# quantum_PSU_V2_3.net
KiCad netlist of a schematic drawn in EAGLE
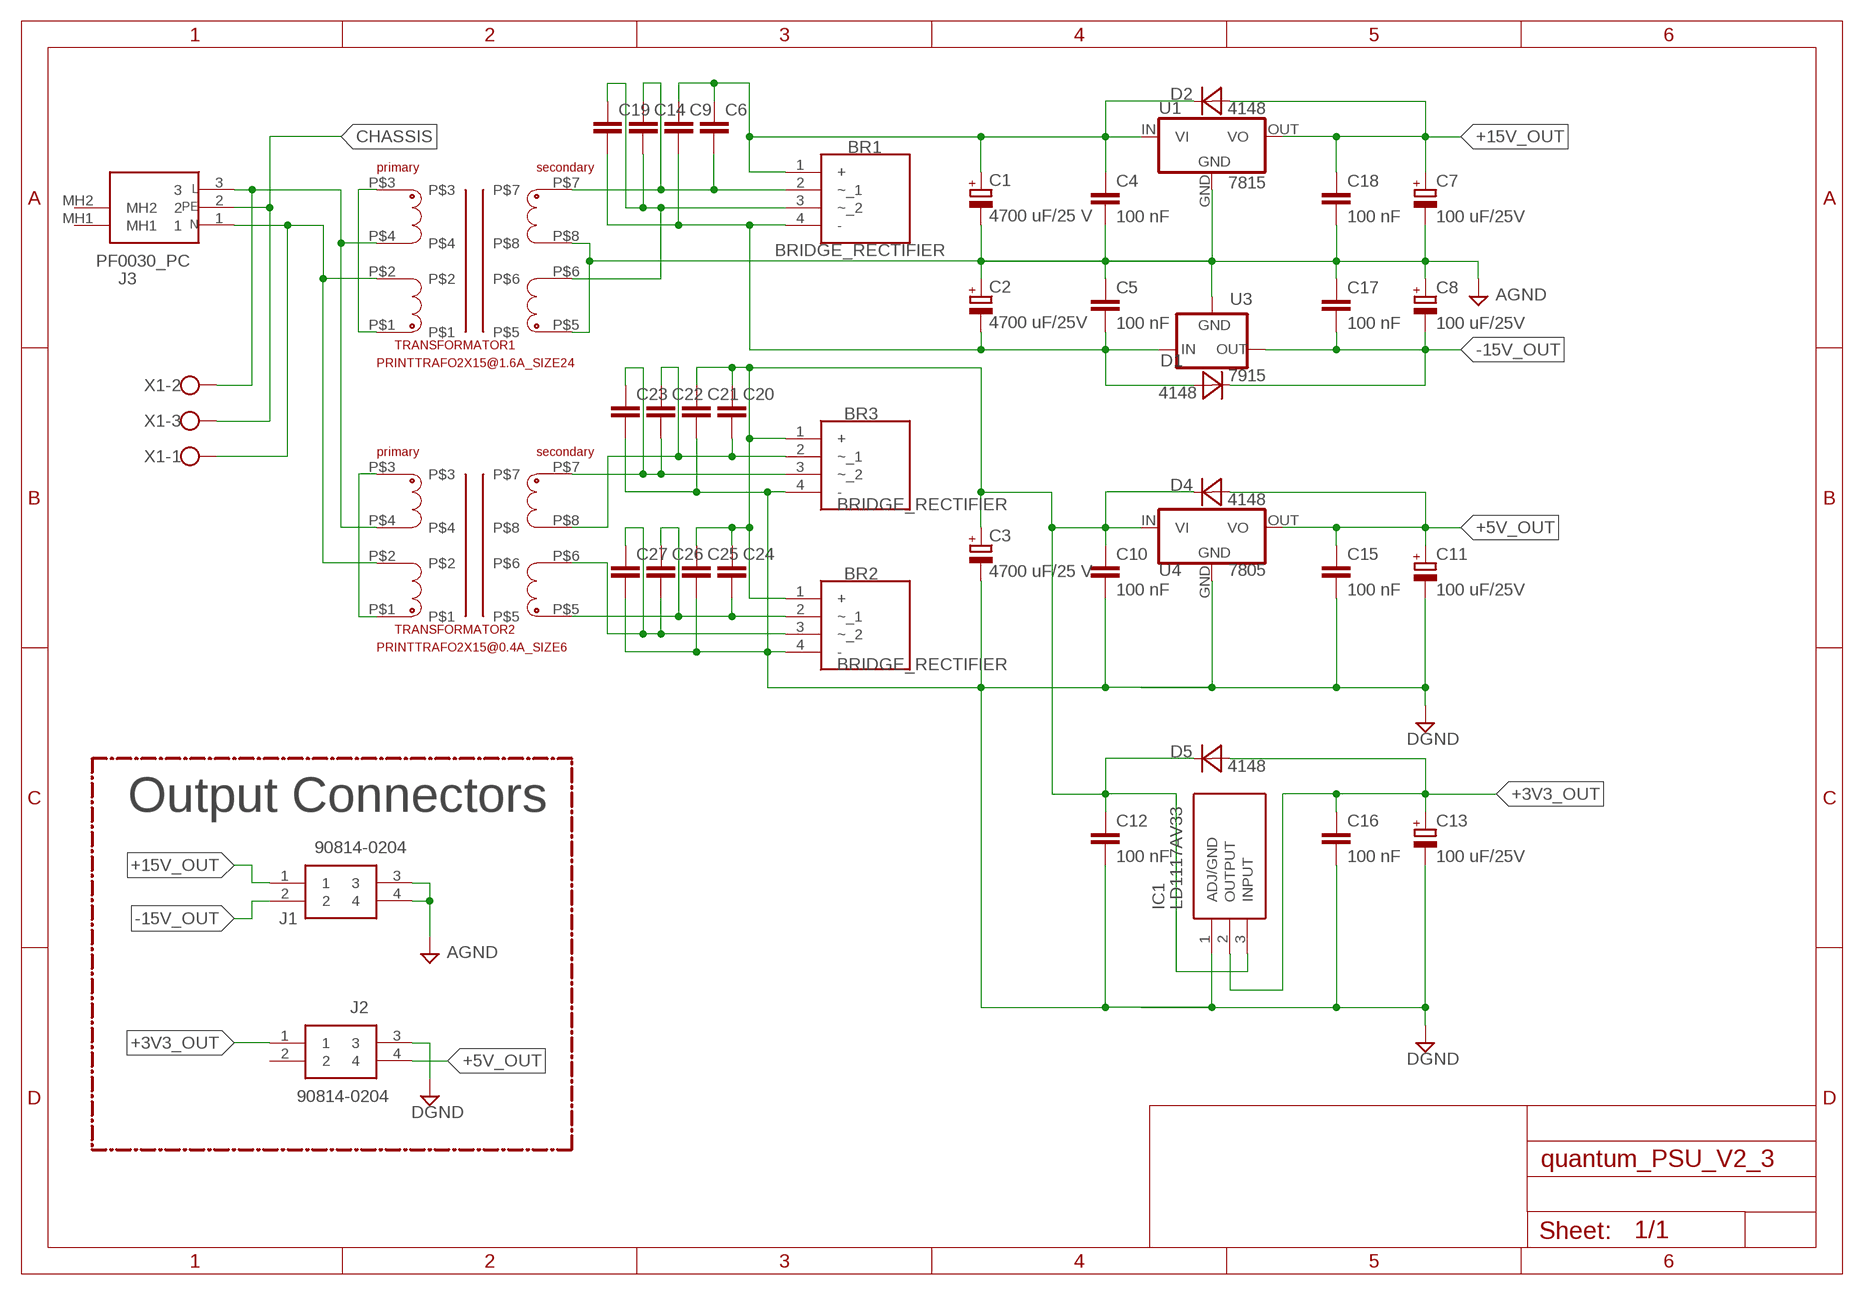
[diagram p0: schematic, sheet 1]

(export (version "E")
  (design (tool "Eeschema 10.0.6"))
  (components
    (comp (ref "BR1")
      (value "BRIDGE_RECTIFIER")
      (footprint "eagle-import:KBP308G")
      (fields
        (field (name "MANUFACTURER_PART_NUMBER") "KBP308G")
        (field (name "MOUSER_PART_NUMBER") "621-KBP308G")
      )
      (libsource (lib "eagle-import") (part "BRIDGE_RECTIFIER"))
    )
    (comp (ref "BR2")
      (value "BRIDGE_RECTIFIER")
      (footprint "eagle-import:KBP308G")
      (fields
        (field (name "MANUFACTURER_PART_NUMBER") "KBP308G")
        (field (name "MOUSER_PART_NUMBER") "621-KBP308G")
      )
      (libsource (lib "eagle-import") (part "BRIDGE_RECTIFIER"))
    )
    (comp (ref "BR3")
      (value "BRIDGE_RECTIFIER")
      (footprint "eagle-import:KBP308G")
      (fields
        (field (name "MANUFACTURER_PART_NUMBER") "KBP308G")
        (field (name "MOUSER_PART_NUMBER") "621-KBP308G")
      )
      (libsource (lib "eagle-import") (part "BRIDGE_RECTIFIER"))
    )
    (comp (ref "C1")
      (value "4700 uF/25 V")
      (footprint "eagle-import:ELECTROLYTIC_16MM")
      (libsource (lib "eagle-import") (part "CAPACITOR_ELECTROLYTIC_16MM-THT"))
    )
    (comp (ref "C2")
      (value "4700 uF/25V")
      (footprint "eagle-import:ELECTROLYTIC_16MM")
      (libsource (lib "eagle-import") (part "CAPACITOR_ELECTROLYTIC_16MM-THT"))
    )
    (comp (ref "C3")
      (value "4700 uF/25 V")
      (footprint "eagle-import:ELECTROLYTIC_16MM")
      (libsource (lib "eagle-import") (part "CAPACITOR_ELECTROLYTIC_16MM-THT"))
    )
    (comp (ref "C4")
      (value "100 nF")
      (footprint "eagle-import:C5MM")
      (libsource (lib "eagle-import") (part "CAPACITOR_5MM"))
    )
    (comp (ref "C5")
      (value "100 nF")
      (footprint "eagle-import:C5MM")
      (libsource (lib "eagle-import") (part "CAPACITOR_5MM"))
    )
    (comp (ref "C6")
      (value "CAPACITOR_2.5MM")
      (footprint "eagle-import:C2.5MM")
      (libsource (lib "eagle-import") (part "CAPACITOR_2.5MM"))
    )
    (comp (ref "C7")
      (value "100 uF/25V")
      (footprint "eagle-import:ELECTROLYTIC_8MM")
      (libsource (lib "eagle-import") (part "CAPACITOR_ELECTROLYTIC_8MM-THT"))
    )
    (comp (ref "C8")
      (value "100 uF/25V")
      (footprint "eagle-import:ELECTROLYTIC_8MM")
      (libsource (lib "eagle-import") (part "CAPACITOR_ELECTROLYTIC_8MM-THT"))
    )
    (comp (ref "C9")
      (value "CAPACITOR_2.5MM")
      (footprint "eagle-import:C2.5MM")
      (libsource (lib "eagle-import") (part "CAPACITOR_2.5MM"))
    )
    (comp (ref "C10")
      (value "100 nF")
      (footprint "eagle-import:C5MM")
      (libsource (lib "eagle-import") (part "CAPACITOR_5MM"))
    )
    (comp (ref "C11")
      (value "100 uF/25V")
      (footprint "eagle-import:ELECTROLYTIC_8MM")
      (libsource (lib "eagle-import") (part "CAPACITOR_ELECTROLYTIC_8MM-THT"))
    )
    (comp (ref "C12")
      (value "100 nF")
      (footprint "eagle-import:C5MM")
      (libsource (lib "eagle-import") (part "CAPACITOR_5MM"))
    )
    (comp (ref "C13")
      (value "100 uF/25V")
      (footprint "eagle-import:ELECTROLYTIC_8MM")
      (libsource (lib "eagle-import") (part "CAPACITOR_ELECTROLYTIC_8MM-THT"))
    )
    (comp (ref "C14")
      (value "CAPACITOR_2.5MM")
      (footprint "eagle-import:C2.5MM")
      (libsource (lib "eagle-import") (part "CAPACITOR_2.5MM"))
    )
    (comp (ref "C15")
      (value "100 nF")
      (footprint "eagle-import:C5MM")
      (libsource (lib "eagle-import") (part "CAPACITOR_5MM"))
    )
    (comp (ref "C16")
      (value "100 nF")
      (footprint "eagle-import:C5MM")
      (libsource (lib "eagle-import") (part "CAPACITOR_5MM"))
    )
    (comp (ref "C17")
      (value "100 nF")
      (footprint "eagle-import:C5MM")
      (libsource (lib "eagle-import") (part "CAPACITOR_5MM"))
    )
    (comp (ref "C18")
      (value "100 nF")
      (footprint "eagle-import:C5MM")
      (libsource (lib "eagle-import") (part "CAPACITOR_5MM"))
    )
    (comp (ref "C19")
      (value "CAPACITOR_2.5MM")
      (footprint "eagle-import:C2.5MM")
      (libsource (lib "eagle-import") (part "CAPACITOR_2.5MM"))
    )
    (comp (ref "C20")
      (value "CAPACITOR_2.5MM")
      (footprint "eagle-import:C2.5MM")
      (libsource (lib "eagle-import") (part "CAPACITOR_2.5MM"))
    )
    (comp (ref "C21")
      (value "CAPACITOR_2.5MM")
      (footprint "eagle-import:C2.5MM")
      (libsource (lib "eagle-import") (part "CAPACITOR_2.5MM"))
    )
    (comp (ref "C22")
      (value "CAPACITOR_2.5MM")
      (footprint "eagle-import:C2.5MM")
      (libsource (lib "eagle-import") (part "CAPACITOR_2.5MM"))
    )
    (comp (ref "C23")
      (value "CAPACITOR_2.5MM")
      (footprint "eagle-import:C2.5MM")
      (libsource (lib "eagle-import") (part "CAPACITOR_2.5MM"))
    )
    (comp (ref "C24")
      (value "CAPACITOR_2.5MM")
      (footprint "eagle-import:C2.5MM")
      (libsource (lib "eagle-import") (part "CAPACITOR_2.5MM"))
    )
    (comp (ref "C25")
      (value "CAPACITOR_2.5MM")
      (footprint "eagle-import:C2.5MM")
      (libsource (lib "eagle-import") (part "CAPACITOR_2.5MM"))
    )
    (comp (ref "C26")
      (value "CAPACITOR_2.5MM")
      (footprint "eagle-import:C2.5MM")
      (libsource (lib "eagle-import") (part "CAPACITOR_2.5MM"))
    )
    (comp (ref "C27")
      (value "CAPACITOR_2.5MM")
      (footprint "eagle-import:C2.5MM")
      (libsource (lib "eagle-import") (part "CAPACITOR_2.5MM"))
    )
    (comp (ref "D1")
      (value "4148")
      (footprint "eagle-import:DIODE_THT_STANDING")
      (fields (field (name "MOUSER_PART_NUMBER") "..."))
      (libsource (lib "eagle-import") (part "DIODE_4148_THT"))
    )
    (comp (ref "D2")
      (value "4148")
      (footprint "eagle-import:DIODE_THT_STANDING")
      (fields (field (name "MOUSER_PART_NUMBER") "..."))
      (libsource (lib "eagle-import") (part "DIODE_4148_THT"))
    )
    (comp (ref "D4")
      (value "4148")
      (footprint "eagle-import:DIODE_THT_STANDING")
      (fields (field (name "MOUSER_PART_NUMBER") "..."))
      (libsource (lib "eagle-import") (part "DIODE_4148_THT"))
    )
    (comp (ref "D5")
      (value "4148")
      (footprint "eagle-import:DIODE_THT_STANDING")
      (fields (field (name "MOUSER_PART_NUMBER") "..."))
      (libsource (lib "eagle-import") (part "DIODE_4148_THT"))
    )
    (comp (ref "IC1")
      (value "LD1117AV33")
      (footprint "eagle-import:TO255P460X1020X2008-3P")
      (fields (field (name "MOUSER_PART_NUMBER") "511-LD1117AV33"))
      (libsource (lib "eagle-import") (part "LD1117AV33"))
    )
    (comp (ref "J1")
      (value "90814-0204")
      (footprint "eagle-import:MOLEX_90814-0204")
      (fields (field (name "MOUSER_PART_NUMBER") "538-90814-0204"))
      (libsource (lib "eagle-import") (part "90814-0204"))
    )
    (comp (ref "J2")
      (value "90814-0204")
      (footprint "eagle-import:MOLEX_90814-0204")
      (fields (field (name "MOUSER_PART_NUMBER") "538-90814-0204"))
      (libsource (lib "eagle-import") (part "90814-0204"))
    )
    (comp (ref "J3")
      (value "PF0030_PC")
      (footprint "eagle-import:PF0030PC")
      (fields
        (field (name "MANUFACTURER_PART_NUMBER") "PF0030/PC")
        (field (name "MOUSER_PART_NUMBER") "161-PF0030/PC")
      )
      (libsource (lib "eagle-import") (part "PF0030_PC"))
    )
    (comp (ref "TRANSFORMATOR1")
      (value "PRINTTRAFO2X15@1.6A_SIZE24")
      (footprint "eagle-import:LP_SIZE_24")
      (fields (field (name "MOUSER_PART_NUMBER") "530-LP-30-800"))
      (libsource (lib "eagle-import") (part "PRINTTRAFO_SIZE242X15@1.6A"))
    )
    (comp (ref "TRANSFORMATOR2")
      (value "PRINTTRAFO2X15@0.4A_SIZE6")
      (footprint "eagle-import:LP_SIZE_6")
      (fields (field (name "MOUSER_PART_NUMBER") "530-LP-30-200"))
      (libsource (lib "eagle-import") (part "PRINTTRAFO_SIZE62X15@0.4A"))
    )
    (comp (ref "U1")
      (value "7815")
      (footprint "eagle-import:78XXS_")
      (libsource (lib "eagle-import") (part "78_THT"))
    )
    (comp (ref "U3")
      (value "7915")
      (footprint "eagle-import:79XXS")
      (libsource (lib "eagle-import") (part "79_THT"))
    )
    (comp (ref "U4")
      (value "7805")
      (footprint "eagle-import:78XXS_")
      (libsource (lib "eagle-import") (part "78_THT"))
    )
    (comp (ref "X1")
      (value "CONNECTOR_3POL")
      (footprint "eagle-import:W237-103")
      (libsource (lib "eagle-import") (part "CONNECTOR_3POL"))
    )
  )
  (nets
    (net (code "1") (name "+3V3_OUT") (class "Default")
      (node (ref "C13") (pin "+") (pinfunction "+_+") (pintype "passive"))
      (node (ref "C16") (pin "1") (pinfunction "1_1") (pintype "passive"))
      (node (ref "D5") (pin "A") (pinfunction "A_A") (pintype "passive"))
      (node (ref "IC1") (pin "2") (pinfunction "OUTPUT_2") (pintype "bidirectional"))
      (node (ref "J2") (pin "1") (pinfunction "1_1") (pintype "bidirectional"))
    )
    (net (code "2") (name "+5V_OUT") (class "Default")
      (node (ref "C11") (pin "+") (pinfunction "+_+") (pintype "passive"))
      (node (ref "C15") (pin "1") (pinfunction "1_1") (pintype "passive"))
      (node (ref "D4") (pin "A") (pinfunction "A_A") (pintype "passive"))
      (node (ref "J2") (pin "4") (pinfunction "4_4") (pintype "bidirectional"))
      (node (ref "U4") (pin "OUT") (pinfunction "VO_OUT") (pintype "passive"))
    )
    (net (code "3") (name "+15V_OUT") (class "Default")
      (node (ref "C18") (pin "1") (pinfunction "1_1") (pintype "passive"))
      (node (ref "C7") (pin "+") (pinfunction "+_+") (pintype "passive"))
      (node (ref "D2") (pin "A") (pinfunction "A_A") (pintype "passive"))
      (node (ref "J1") (pin "1") (pinfunction "1_1") (pintype "bidirectional"))
      (node (ref "U1") (pin "OUT") (pinfunction "VO_OUT") (pintype "passive"))
    )
    (net (code "4") (name "-15V_OUT") (class "Default")
      (node (ref "C17") (pin "2") (pinfunction "2_2") (pintype "passive"))
      (node (ref "C8") (pin "-") (pinfunction "-_-") (pintype "passive"))
      (node (ref "D1") (pin "C") (pinfunction "C_C") (pintype "passive"))
      (node (ref "J1") (pin "2") (pinfunction "2_2") (pintype "bidirectional"))
      (node (ref "U3") (pin "OUT") (pinfunction "OUT_OUT") (pintype "passive"))
    )
    (net (code "5") (name "AGND") (class "Default")
      (node (ref "C1") (pin "-") (pinfunction "-_-") (pintype "passive"))
      (node (ref "C17") (pin "1") (pinfunction "1_1") (pintype "passive"))
      (node (ref "C18") (pin "2") (pinfunction "2_2") (pintype "passive"))
      (node (ref "C2") (pin "+") (pinfunction "+_+") (pintype "passive"))
      (node (ref "C4") (pin "2") (pinfunction "2_2") (pintype "passive"))
      (node (ref "C5") (pin "1") (pinfunction "1_1") (pintype "passive"))
      (node (ref "C7") (pin "-") (pinfunction "-_-") (pintype "passive"))
      (node (ref "C8") (pin "+") (pinfunction "+_+") (pintype "passive"))
      (node (ref "J1") (pin "3") (pinfunction "3_3") (pintype "bidirectional"))
      (node (ref "J1") (pin "4") (pinfunction "4_4") (pintype "bidirectional"))
      (node (ref "TRANSFORMATOR1") (pin "P$5") (pinfunction "P$5_P$5") (pintype "bidirectional"))
      (node (ref "TRANSFORMATOR1") (pin "P$8") (pinfunction "P$8_P$8") (pintype "bidirectional"))
      (node (ref "U1") (pin "GND") (pinfunction "GND_GND") (pintype "passive"))
      (node (ref "U3") (pin "GND") (pinfunction "GND_GND") (pintype "input"))
    )
    (net (code "6") (name "CHASSIS") (class "Default")
      (node (ref "J3") (pin "2") (pinfunction "2_2") (pintype "bidirectional"))
      (node (ref "X1") (pin "3") (pinfunction "KL_3") (pintype "passive"))
    )
    (net (code "7") (name "DGND") (class "Default")
      (node (ref "BR2") (pin "4") (pinfunction "-_4") (pintype "bidirectional"))
      (node (ref "BR3") (pin "4") (pinfunction "-_4") (pintype "bidirectional"))
      (node (ref "C10") (pin "2") (pinfunction "2_2") (pintype "passive"))
      (node (ref "C11") (pin "-") (pinfunction "-_-") (pintype "passive"))
      (node (ref "C12") (pin "2") (pinfunction "2_2") (pintype "passive"))
      (node (ref "C13") (pin "-") (pinfunction "-_-") (pintype "passive"))
      (node (ref "C15") (pin "2") (pinfunction "2_2") (pintype "passive"))
      (node (ref "C16") (pin "2") (pinfunction "2_2") (pintype "passive"))
      (node (ref "C21") (pin "2") (pinfunction "2_2") (pintype "passive"))
      (node (ref "C23") (pin "2") (pinfunction "2_2") (pintype "passive"))
      (node (ref "C25") (pin "2") (pinfunction "2_2") (pintype "passive"))
      (node (ref "C27") (pin "2") (pinfunction "2_2") (pintype "passive"))
      (node (ref "C3") (pin "-") (pinfunction "-_-") (pintype "passive"))
      (node (ref "IC1") (pin "1") (pinfunction "ADJ/GND_1") (pintype "bidirectional"))
      (node (ref "J2") (pin "3") (pinfunction "3_3") (pintype "bidirectional"))
      (node (ref "U4") (pin "GND") (pinfunction "GND_GND") (pintype "passive"))
    )
    (net (code "8") (name "Net-(BR1-+)") (class "Default")
      (node (ref "BR1") (pin "1") (pinfunction "+_1") (pintype "bidirectional"))
      (node (ref "C1") (pin "+") (pinfunction "+_+") (pintype "passive"))
      (node (ref "C4") (pin "1") (pinfunction "1_1") (pintype "passive"))
      (node (ref "C6") (pin "1") (pinfunction "1_1") (pintype "passive"))
      (node (ref "C9") (pin "1") (pinfunction "1_1") (pintype "passive"))
      (node (ref "D2") (pin "C") (pinfunction "C_C") (pintype "passive"))
      (node (ref "U1") (pin "IN") (pinfunction "VI_IN") (pintype "input"))
    )
    (net (code "9") (name "Net-(BR1--)") (class "Default")
      (node (ref "BR1") (pin "4") (pinfunction "-_4") (pintype "bidirectional"))
      (node (ref "C19") (pin "2") (pinfunction "2_2") (pintype "passive"))
      (node (ref "C2") (pin "-") (pinfunction "-_-") (pintype "passive"))
      (node (ref "C5") (pin "2") (pinfunction "2_2") (pintype "passive"))
      (node (ref "C9") (pin "2") (pinfunction "2_2") (pintype "passive"))
      (node (ref "D1") (pin "A") (pinfunction "A_A") (pintype "passive"))
      (node (ref "U3") (pin "IN") (pinfunction "IN_IN") (pintype "input"))
    )
    (net (code "10") (name "Net-(BR1-~{_1})") (class "Default")
      (node (ref "BR1") (pin "2") (pinfunction "~{_1}_2") (pintype "bidirectional"))
      (node (ref "C14") (pin "1") (pinfunction "1_1") (pintype "passive"))
      (node (ref "C6") (pin "2") (pinfunction "2_2") (pintype "passive"))
      (node (ref "TRANSFORMATOR1") (pin "P$7") (pinfunction "P$7_P$7") (pintype "bidirectional"))
    )
    (net (code "11") (name "Net-(BR1-~{_2})") (class "Default")
      (node (ref "BR1") (pin "3") (pinfunction "~{_2}_3") (pintype "bidirectional"))
      (node (ref "C14") (pin "2") (pinfunction "2_2") (pintype "passive"))
      (node (ref "C19") (pin "1") (pinfunction "1_1") (pintype "passive"))
      (node (ref "TRANSFORMATOR1") (pin "P$6") (pinfunction "P$6_P$6") (pintype "bidirectional"))
    )
    (net (code "12") (name "Net-(BR2-+)") (class "Default")
      (node (ref "BR2") (pin "1") (pinfunction "+_1") (pintype "bidirectional"))
      (node (ref "BR3") (pin "1") (pinfunction "+_1") (pintype "bidirectional"))
      (node (ref "C10") (pin "1") (pinfunction "1_1") (pintype "passive"))
      (node (ref "C12") (pin "1") (pinfunction "1_1") (pintype "passive"))
      (node (ref "C20") (pin "1") (pinfunction "1_1") (pintype "passive"))
      (node (ref "C21") (pin "1") (pinfunction "1_1") (pintype "passive"))
      (node (ref "C24") (pin "1") (pinfunction "1_1") (pintype "passive"))
      (node (ref "C25") (pin "1") (pinfunction "1_1") (pintype "passive"))
      (node (ref "C3") (pin "+") (pinfunction "+_+") (pintype "passive"))
      (node (ref "D4") (pin "C") (pinfunction "C_C") (pintype "passive"))
      (node (ref "D5") (pin "C") (pinfunction "C_C") (pintype "passive"))
      (node (ref "IC1") (pin "3") (pinfunction "INPUT_3") (pintype "bidirectional"))
      (node (ref "U4") (pin "IN") (pinfunction "VI_IN") (pintype "input"))
    )
    (net (code "13") (name "Net-(BR2-~{_1})") (class "Default")
      (node (ref "BR2") (pin "2") (pinfunction "~{_1}_2") (pintype "bidirectional"))
      (node (ref "C24") (pin "2") (pinfunction "2_2") (pintype "passive"))
      (node (ref "C26") (pin "1") (pinfunction "1_1") (pintype "passive"))
      (node (ref "TRANSFORMATOR2") (pin "P$5") (pinfunction "P$5_P$5") (pintype "bidirectional"))
    )
    (net (code "14") (name "Net-(BR2-~{_2})") (class "Default")
      (node (ref "BR2") (pin "3") (pinfunction "~{_2}_3") (pintype "bidirectional"))
      (node (ref "C26") (pin "2") (pinfunction "2_2") (pintype "passive"))
      (node (ref "C27") (pin "1") (pinfunction "1_1") (pintype "passive"))
      (node (ref "TRANSFORMATOR2") (pin "P$6") (pinfunction "P$6_P$6") (pintype "bidirectional"))
    )
    (net (code "15") (name "Net-(BR3-~{_1})") (class "Default")
      (node (ref "BR3") (pin "2") (pinfunction "~{_1}_2") (pintype "bidirectional"))
      (node (ref "C20") (pin "2") (pinfunction "2_2") (pintype "passive"))
      (node (ref "C22") (pin "1") (pinfunction "1_1") (pintype "passive"))
      (node (ref "TRANSFORMATOR2") (pin "P$8") (pinfunction "P$8_P$8") (pintype "bidirectional"))
    )
    (net (code "16") (name "Net-(BR3-~{_2})") (class "Default")
      (node (ref "BR3") (pin "3") (pinfunction "~{_2}_3") (pintype "bidirectional"))
      (node (ref "C22") (pin "2") (pinfunction "2_2") (pintype "passive"))
      (node (ref "C23") (pin "1") (pinfunction "1_1") (pintype "passive"))
      (node (ref "TRANSFORMATOR2") (pin "P$7") (pinfunction "P$7_P$7") (pintype "bidirectional"))
    )
    (net (code "17") (name "Net-(TRANSFORMATOR1-PadP$1)") (class "Default")
      (node (ref "TRANSFORMATOR1") (pin "P$1") (pinfunction "P$1_P$1") (pintype "bidirectional"))
      (node (ref "TRANSFORMATOR1") (pin "P$3") (pinfunction "P$3_P$3") (pintype "bidirectional"))
    )
    (net (code "18") (name "Net-(TRANSFORMATOR2-PadP$1)") (class "Default")
      (node (ref "TRANSFORMATOR2") (pin "P$1") (pinfunction "P$1_P$1") (pintype "bidirectional"))
      (node (ref "TRANSFORMATOR2") (pin "P$3") (pinfunction "P$3_P$3") (pintype "bidirectional"))
    )
    (net (code "19") (name "Net-(X1A-KL)") (class "Default")
      (node (ref "J3") (pin "1") (pinfunction "1_1") (pintype "bidirectional"))
      (node (ref "TRANSFORMATOR1") (pin "P$2") (pinfunction "P$2_P$2") (pintype "bidirectional"))
      (node (ref "TRANSFORMATOR2") (pin "P$2") (pinfunction "P$2_P$2") (pintype "bidirectional"))
      (node (ref "X1") (pin "1") (pinfunction "KL_1") (pintype "passive"))
    )
    (net (code "20") (name "Net-(X1B-KL)") (class "Default")
      (node (ref "J3") (pin "3") (pinfunction "3_3") (pintype "bidirectional"))
      (node (ref "TRANSFORMATOR1") (pin "P$4") (pinfunction "P$4_P$4") (pintype "bidirectional"))
      (node (ref "TRANSFORMATOR2") (pin "P$4") (pinfunction "P$4_P$4") (pintype "bidirectional"))
      (node (ref "X1") (pin "2") (pinfunction "KL_2") (pintype "passive"))
    )
    (net (code "21") (name "unconnected-(J2-Pad2)") (class "Default")
      (node (ref "J2") (pin "2") (pinfunction "2_2") (pintype "bidirectional"))
    )
    (net (code "22") (name "unconnected-(J3-PadMH1)") (class "Default")
      (node (ref "J3") (pin "MH1") (pinfunction "MH1_MH1") (pintype "bidirectional"))
    )
    (net (code "23") (name "unconnected-(J3-PadMH2)") (class "Default")
      (node (ref "J3") (pin "MH2") (pinfunction "MH2_MH2") (pintype "bidirectional"))
    )
  )
)
